# PROC051C_CAN_Interface.net
KiCad netlist of a schematic drawn in Altium Designer
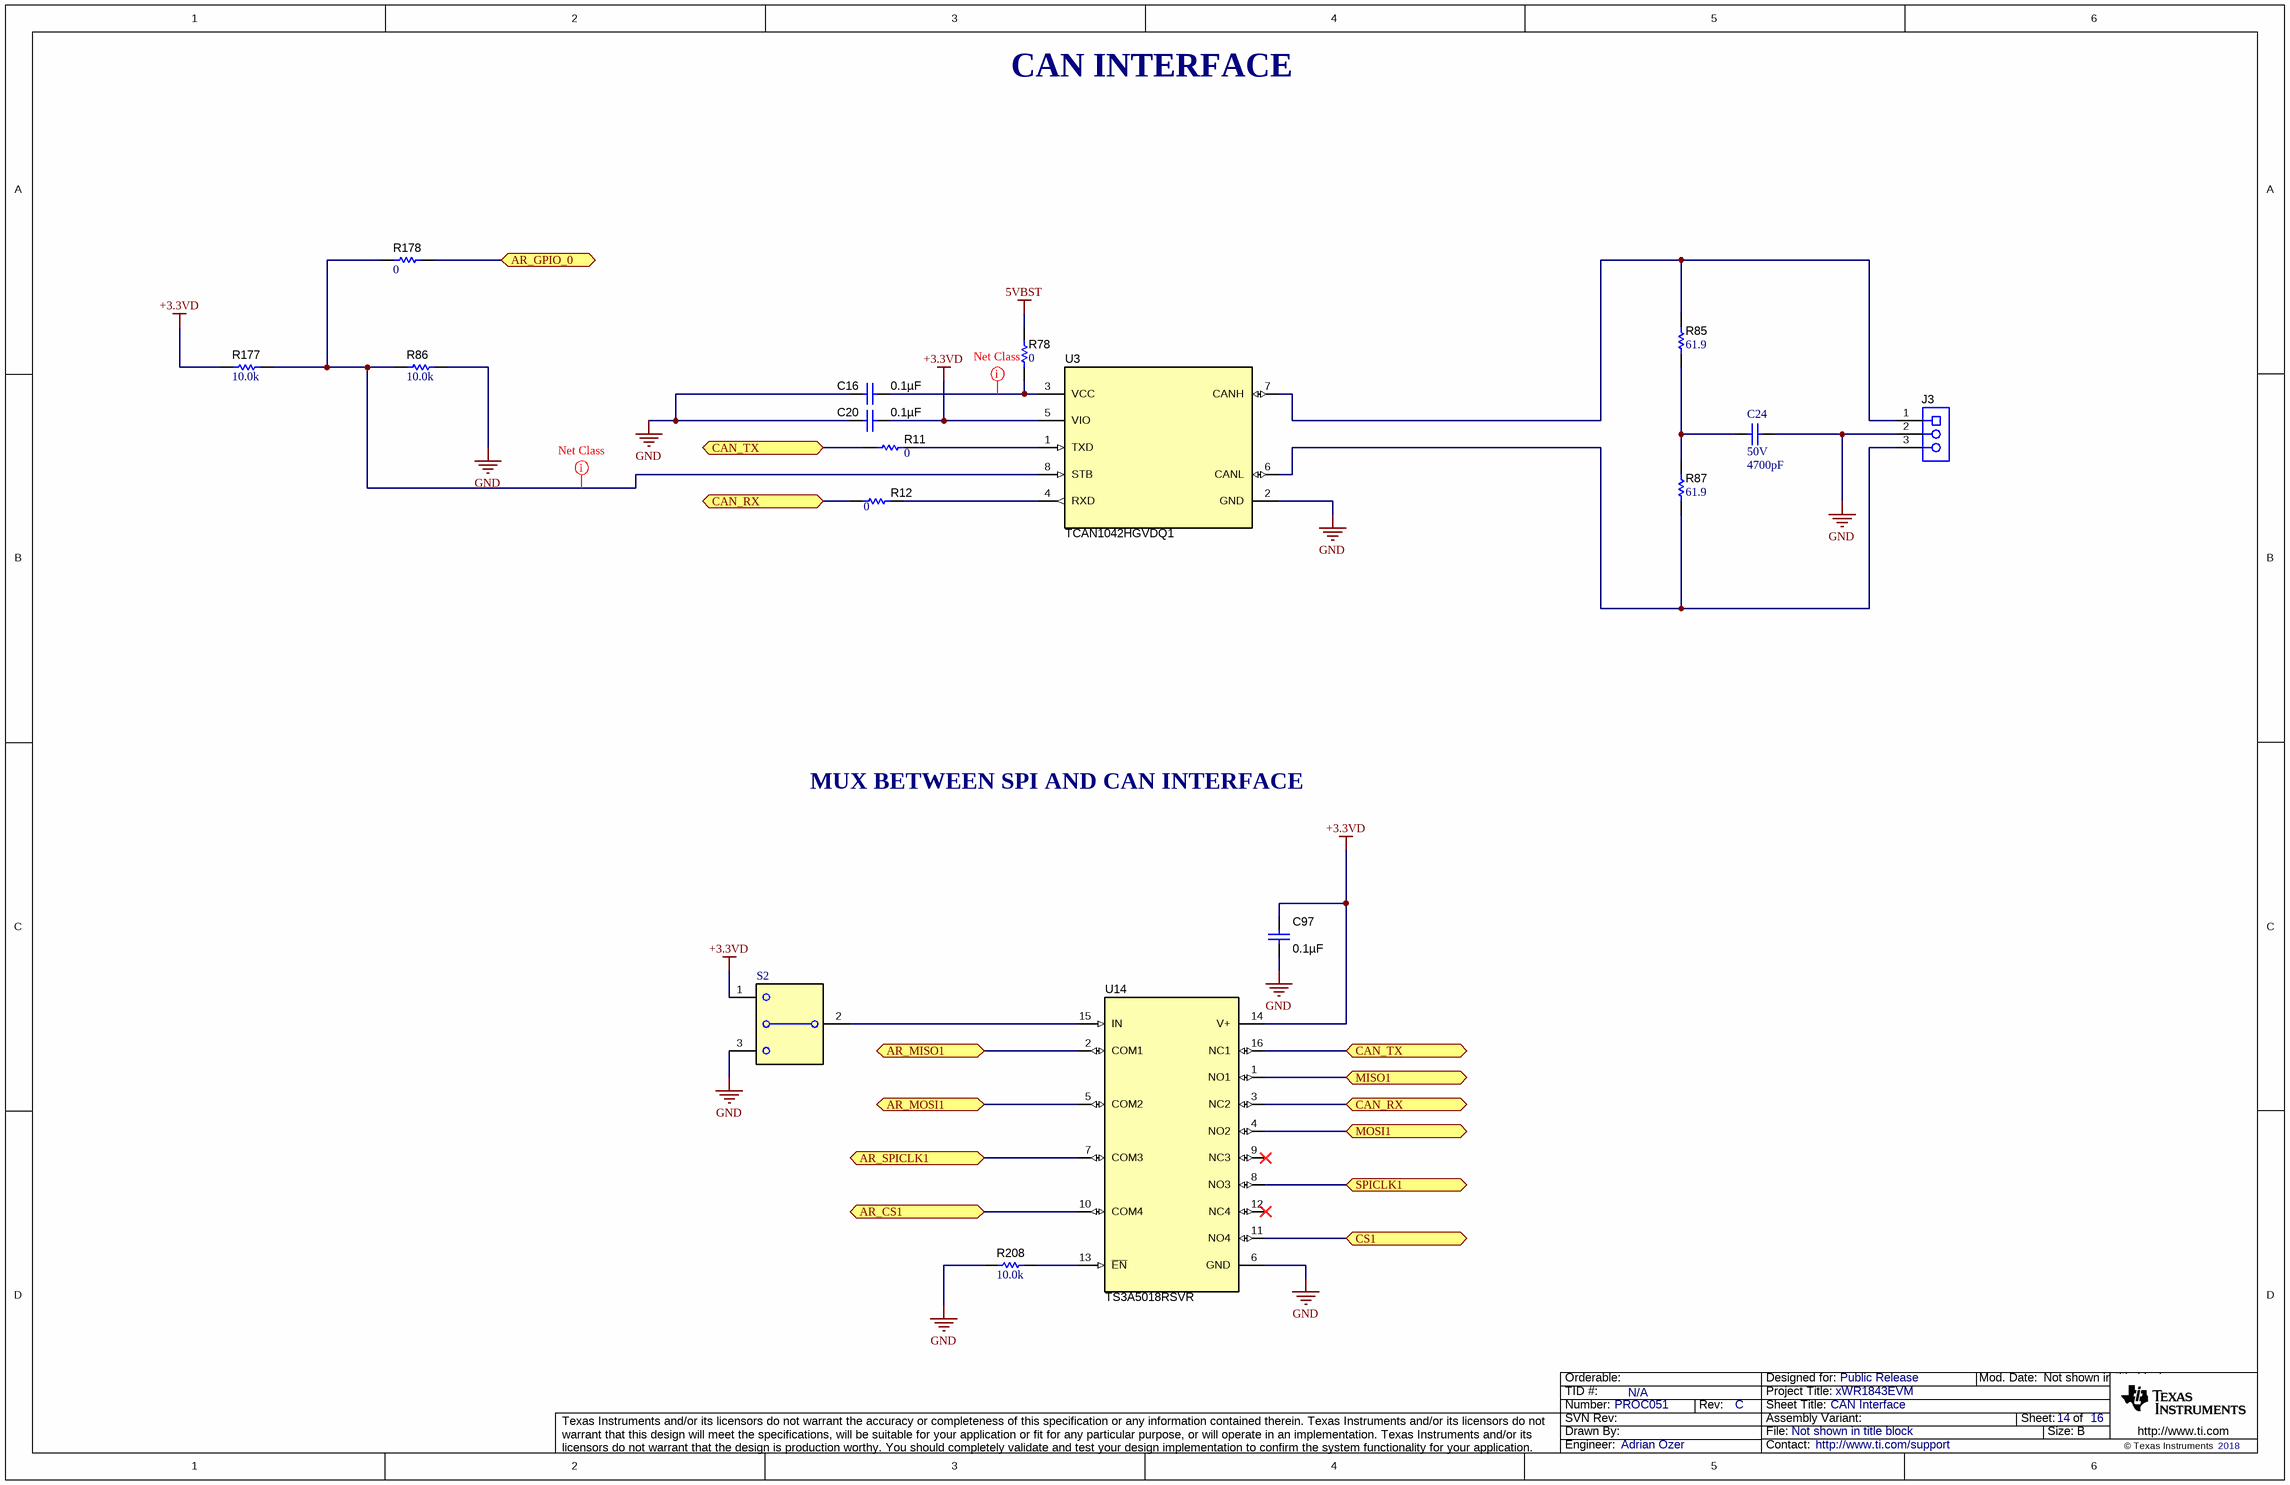
[diagram p0: PROC051C_CAN_Interface.SchDoc]

(export (version "E")
  (design (tool "Eeschema 10.0.6"))
  (components
    (comp (ref "C16")
      (value "C0402C104K8RACTU")
      (footprint "0402L")
      (description "CAP, CERM, 0.1 µF, 10 V,+/- 10%, X7R, 0402")
      (fields (field (name "MANUFACTURER") "Kemet") (field (name "VALUEDISPLAYED") "0.1µF"))
      (libsource (lib "Altium Vault - TI") (part "Capacitor"))
    )
    (comp (ref "C20")
      (value "C0402C104K8RACTU")
      (footprint "0402L")
      (description "CAP, CERM, 0.1 µF, 10 V,+/- 10%, X7R, 0402")
      (fields (field (name "MANUFACTURER") "Kemet") (field (name "VALUEDISPLAYED") "0.1µF"))
      (libsource (lib "Altium Vault - TI") (part "Capacitor"))
    )
    (comp (ref "C24")
      (value "GCM155R71H472KA37D")
      (footprint "0402")
      (description "CAP, CERM, 4700 pF, 50 V, +/- 10%, X7R, AEC-Q200 Grade 1, 0402")
      (fields
        (field (name "MANUFACTURER") "MuRata")
        (field (name "VDC_V") "50V")
        (field (name "VALUEDISPLAYED") "4700pF")
        (field (name "PUBLISHER") "Texas Instruments")
      )
      (libsource (lib "Altium Vault - TI") (part "Capacitor"))
    )
    (comp (ref "C97")
      (value "C0402C104K8RACTU")
      (footprint "0402L")
      (description "CAP, CERM, 0.1 µF, 10 V,+/- 10%, X7R, 0402")
      (fields (field (name "MANUFACTURER") "Kemet") (field (name "VALUEDISPLAYED") "0.1µF"))
      (libsource (lib "Altium Vault - TI") (part "Capacitor"))
    )
    (comp (ref "J3")
      (value "OSTTE030161")
      (footprint "On-Shore_OSTTE030161")
      (description "Terminal Block, 3.5mm, 3x1, Tin, R/A, TH")
      (fields
        (field (name "MANUFACTURER") "On-Shore Technology")
        (field (name "PUBLISHER") "Texas Instruments")
      )
      (libsource (lib "Altium Vault - TI") (part "Receptacle_3x1"))
    )
    (comp (ref "R11")
      (value "0")
      (footprint "0402L")
      (description "RES, 0, 5%, 0.1 W, AEC-Q200 Grade 0, 0402")
      (fields (field (name "MANUFACTURER") "Panasonic") (field (name "PARTNUMBER") "ERJ-2GE0R00X"))
      (libsource (lib "Altium Vault - TI") (part "Resistor"))
    )
    (comp (ref "R12")
      (value "ERJ-2GE0R00X")
      (footprint "0402L")
      (description "RES, 0, 5%, 0.1 W, AEC-Q200 Grade 0, 0402")
      (fields (field (name "MANUFACTURER") "Panasonic") (field (name "VALUEDISPLAYED") "0"))
      (libsource (lib "Altium Vault - TI") (part "Resistor"))
    )
    (comp (ref "R78")
      (value "ERJ-2GE0R00X")
      (footprint "0402L")
      (description "RES, 0, 5%, 0.1 W, AEC-Q200 Grade 0, 0402")
      (fields (field (name "MANUFACTURER") "Panasonic") (field (name "VALUEDISPLAYED") "0"))
      (libsource (lib "Altium Vault - TI") (part "Resistor"))
    )
    (comp (ref "R85")
      (value "CRCW040261R9FKED")
      (footprint "0402L")
      (description "RES, 61.9, 1%, 0.063 W, AEC-Q200 Grade 0, 0402")
      (fields (field (name "MANUFACTURER") "Vishay-Dale") (field (name "VALUEDISPLAYED") "61.9"))
      (libsource (lib "Altium Vault - TI") (part "Resistor"))
    )
    (comp (ref "R86")
      (value "CRCW040210K0FKED")
      (footprint "0402L")
      (description "RES, 10.0 k, 1%, 0.063 W, AEC-Q200 Grade 0, 0402")
      (fields (field (name "MANUFACTURER") "Vishay-Dale") (field (name "VALUEDISPLAYED") "10.0k"))
      (libsource (lib "Altium Vault - TI") (part "Resistor"))
    )
    (comp (ref "R87")
      (value "CRCW040261R9FKED")
      (footprint "0402L")
      (description "RES, 61.9, 1%, 0.063 W, AEC-Q200 Grade 0, 0402")
      (fields (field (name "MANUFACTURER") "Vishay-Dale") (field (name "VALUEDISPLAYED") "61.9"))
      (libsource (lib "Altium Vault - TI") (part "Resistor"))
    )
    (comp (ref "R177")
      (value "CRCW040210K0FKED")
      (footprint "0402L")
      (description "RES, 10.0 k, 1%, 0.063 W, AEC-Q200 Grade 0, 0402")
      (fields (field (name "MANUFACTURER") "Vishay-Dale") (field (name "VALUEDISPLAYED") "10.0k"))
      (libsource (lib "Altium Vault - TI") (part "Resistor"))
    )
    (comp (ref "R178")
      (value "ERJ-2GE0R00X")
      (footprint "0402L")
      (description "RES, 0, 5%, 0.1 W, AEC-Q200 Grade 0, 0402")
      (fields (field (name "MANUFACTURER") "Panasonic") (field (name "VALUEDISPLAYED") "0"))
      (libsource (lib "Altium Vault - TI") (part "Resistor"))
    )
    (comp (ref "R208")
      (value "CRCW040210K0FKED")
      (footprint "0402L")
      (description "RES, 10.0 k, 1%, 0.063 W, AEC-Q200 Grade 0, 0402")
      (fields (field (name "MANUFACTURER") "Vishay-Dale") (field (name "VALUEDISPLAYED") "10.0k"))
      (libsource (lib "Altium Vault - TI") (part "Resistor"))
    )
    (comp (ref "S2")
      (value "CJS-1201TA")
      (footprint "SW_CJS_1201A")
      (description "Slide SW, SPDT 0.1A 50VDC")
      (fields
        (field (name "MANUFACTURER") "Copal Electronics")
        (field (name "PUBLISHER") "Texas Instruments")
      )
      (libsource (lib "Altium Vault - TI") (part "SW_SPDT_ON-OFF-ON_COM2_1_3"))
    )
    (comp (ref "U3")
      (value "TCAN1042HGVDQ1")
      (footprint "D0008A_L")
      (description "Automotive Fault Protected CAN Transceiver With Flexible Data-Rate, D0008A (SOIC-8)")
      (fields
        (field (name "PARTNUMBER") "TCAN1042HGVDQ1")
        (field (name "MANUFACTURER") "Texas Instruments")
        (field (name "ALTERNATE PARTNUMBER") "TCAN1042HGVDRQ1")
        (field (name "PUBLISHER") "Texas Instruments")
      )
      (libsource (lib "Altium Vault - TI") (part "TCAN1042_V"))
    )
    (comp (ref "U14")
      (value "TS3A5018RSVR")
      (footprint "RSV0016A")
      (description "10-Ohm Quad SPDT Analog Switch, RSV0016A (UQFN-16)")
      (fields
        (field (name "MANUFACTURER") "Texas Instruments")
        (field (name "PARTNUMBER") "TS3A5018RSVR")
        (field (name "PUBLISHER") "Texas Instruments")
      )
      (libsource (lib "Altium Vault - TI") (part "CMP-0067415-1"))
    )
  )
  (nets
    (net (code "1") (name "+3.3VD") (class "Default")
      (node (ref "C20") (pin "2") (pinfunction "2_2") (pintype "passive"))
      (node (ref "C97") (pin "2") (pinfunction "2_2") (pintype "passive"))
      (node (ref "R177") (pin "1") (pinfunction "1_1") (pintype "passive"))
      (node (ref "S2") (pin "1") (pinfunction "1_1") (pintype "passive"))
      (node (ref "U14") (pin "14") (pinfunction "V+_14") (pintype "power_in"))
      (node (ref "U3") (pin "5") (pinfunction "VIO_5") (pintype "power_in"))
    )
    (net (code "2") (name "/AR_CS1") (class "Default")
      (node (ref "U14") (pin "10") (pinfunction "COM4_10") (pintype "bidirectional"))
    )
    (net (code "3") (name "/AR_GPIO_0") (class "Default")
      (node (ref "R178") (pin "2") (pinfunction "2_2") (pintype "passive"))
    )
    (net (code "4") (name "/AR_MISO1") (class "Default")
      (node (ref "U14") (pin "2") (pinfunction "COM1_2") (pintype "bidirectional"))
    )
    (net (code "5") (name "/AR_MOSI1") (class "Default")
      (node (ref "U14") (pin "5") (pinfunction "COM2_5") (pintype "bidirectional"))
    )
    (net (code "6") (name "/AR_SPICLK1") (class "Default")
      (node (ref "U14") (pin "7") (pinfunction "COM3_7") (pintype "bidirectional"))
    )
    (net (code "7") (name "/CAN_RX") (class "Default")
      (node (ref "R12") (pin "1") (pinfunction "1_1") (pintype "passive"))
      (node (ref "U14") (pin "3") (pinfunction "NC2_3") (pintype "bidirectional"))
    )
    (net (code "8") (name "/CAN_TX") (class "Default")
      (node (ref "R11") (pin "1") (pinfunction "1_1") (pintype "passive"))
      (node (ref "U14") (pin "16") (pinfunction "NC1_16") (pintype "bidirectional"))
    )
    (net (code "9") (name "/CS1") (class "Default")
      (node (ref "U14") (pin "11") (pinfunction "NO4_11") (pintype "bidirectional"))
    )
    (net (code "10") (name "/MISO1") (class "Default")
      (node (ref "U14") (pin "1") (pinfunction "NO1_1") (pintype "bidirectional"))
    )
    (net (code "11") (name "/MOSI1") (class "Default")
      (node (ref "U14") (pin "4") (pinfunction "NO2_4") (pintype "bidirectional"))
    )
    (net (code "12") (name "/SPICLK1") (class "Default")
      (node (ref "U14") (pin "8") (pinfunction "NO3_8") (pintype "bidirectional"))
    )
    (net (code "13") (name "5VBST") (class "Default")
      (node (ref "R78") (pin "2") (pinfunction "2_2") (pintype "passive"))
    )
    (net (code "14") (name "GND") (class "Default")
      (node (ref "C16") (pin "1") (pinfunction "1_1") (pintype "passive"))
      (node (ref "C20") (pin "1") (pinfunction "1_1") (pintype "passive"))
      (node (ref "C24") (pin "1") (pinfunction "1_1") (pintype "passive"))
      (node (ref "C97") (pin "1") (pinfunction "1_1") (pintype "passive"))
      (node (ref "J3") (pin "2") (pinfunction "2_2") (pintype "passive"))
      (node (ref "R208") (pin "2") (pinfunction "2_2") (pintype "passive"))
      (node (ref "R86") (pin "2") (pinfunction "2_2") (pintype "passive"))
      (node (ref "S2") (pin "3") (pinfunction "3_3") (pintype "passive"))
      (node (ref "U14") (pin "6") (pinfunction "GND_6") (pintype "power_in"))
      (node (ref "U3") (pin "2") (pinfunction "GND_2") (pintype "power_in"))
    )
    (net (code "15") (name "Net-(C24-Pad2)") (class "Default")
      (node (ref "C24") (pin "2") (pinfunction "2_2") (pintype "passive"))
      (node (ref "R85") (pin "1") (pinfunction "1_1") (pintype "passive"))
      (node (ref "R87") (pin "2") (pinfunction "2_2") (pintype "passive"))
    )
    (net (code "16") (name "Net-(S2-COM)") (class "Default")
      (node (ref "S2") (pin "2") (pinfunction "COM_2") (pintype "passive"))
      (node (ref "U14") (pin "15") (pinfunction "IN_15") (pintype "input"))
    )
    (net (code "17") (name "Net-(U3-CANH)") (class "Default")
      (node (ref "J3") (pin "1") (pinfunction "1_1") (pintype "passive"))
      (node (ref "R85") (pin "2") (pinfunction "2_2") (pintype "passive"))
      (node (ref "U3") (pin "7") (pinfunction "CANH_7") (pintype "bidirectional"))
    )
    (net (code "18") (name "Net-(U3-CANL)") (class "Default")
      (node (ref "J3") (pin "3") (pinfunction "3_3") (pintype "passive"))
      (node (ref "R87") (pin "1") (pinfunction "1_1") (pintype "passive"))
      (node (ref "U3") (pin "6") (pinfunction "CANL_6") (pintype "bidirectional"))
    )
    (net (code "19") (name "Net-(U3-RXD)") (class "Default")
      (node (ref "R12") (pin "2") (pinfunction "2_2") (pintype "passive"))
      (node (ref "U3") (pin "4") (pinfunction "RXD_4") (pintype "output"))
    )
    (net (code "20") (name "Net-(U3-STB)") (class "Default")
      (node (ref "R177") (pin "2") (pinfunction "2_2") (pintype "passive"))
      (node (ref "R178") (pin "1") (pinfunction "1_1") (pintype "passive"))
      (node (ref "R86") (pin "1") (pinfunction "1_1") (pintype "passive"))
      (node (ref "U3") (pin "8") (pinfunction "STB_8") (pintype "input"))
    )
    (net (code "21") (name "Net-(U3-TXD)") (class "Default")
      (node (ref "R11") (pin "2") (pinfunction "2_2") (pintype "passive"))
      (node (ref "U3") (pin "1") (pinfunction "TXD_1") (pintype "input"))
    )
    (net (code "22") (name "Net-(U3-VCC)") (class "Default")
      (node (ref "C16") (pin "2") (pinfunction "2_2") (pintype "passive"))
      (node (ref "R78") (pin "1") (pinfunction "1_1") (pintype "passive"))
      (node (ref "U3") (pin "3") (pinfunction "VCC_3") (pintype "power_in"))
    )
    (net (code "23") (name "Net-(U14-EN)") (class "Default")
      (node (ref "R208") (pin "1") (pinfunction "1_1") (pintype "passive"))
      (node (ref "U14") (pin "13") (pinfunction "EN_13") (pintype "input"))
    )
    (net (code "24") (name "unconnected-(U14-NC3-Pad9)") (class "Default")
      (node (ref "U14") (pin "9") (pinfunction "NC3_9") (pintype "bidirectional+no_connect"))
    )
    (net (code "25") (name "unconnected-(U14-NC4-Pad12)") (class "Default")
      (node (ref "U14") (pin "12") (pinfunction "NC4_12") (pintype "bidirectional+no_connect"))
    )
  )
)
